# V2_0.net
KiCad netlist of a schematic drawn in EAGLE
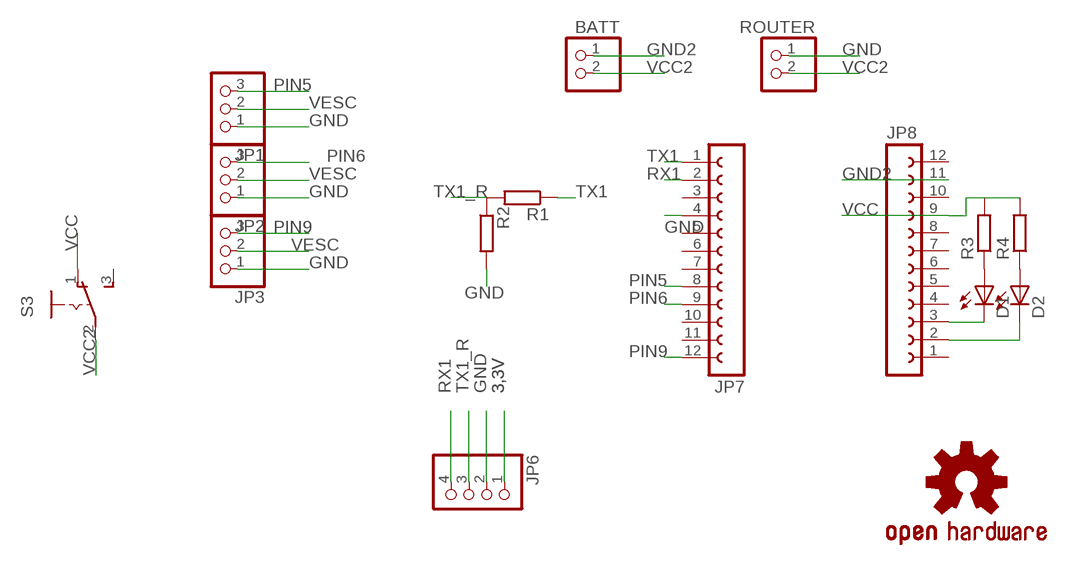
[diagram p0: schematic, sheet 1]

(export (version "E")
  (design (tool "Eeschema 10.0.6"))
  (components
    (comp (ref "BATT")
      (value "PINHD-1X2/90")
      (footprint "eagle-import:1X02_90")
      (libsource (lib "eagle-import") (part "PINHD-1X2/90"))
    )
    (comp (ref "D1")
      (value "LED3MM")
      (footprint "eagle-import:LED3MM")
      (libsource (lib "eagle-import") (part "LED3MM"))
    )
    (comp (ref "D2")
      (value "LED3MM")
      (footprint "eagle-import:LED3MM")
      (libsource (lib "eagle-import") (part "LED3MM"))
    )
    (comp (ref "JP1")
      (value "PINHD-1X3")
      (footprint "eagle-import:1X03")
      (libsource (lib "eagle-import") (part "PINHD-1X3"))
    )
    (comp (ref "JP2")
      (value "PINHD-1X3")
      (footprint "eagle-import:1X03")
      (libsource (lib "eagle-import") (part "PINHD-1X3"))
    )
    (comp (ref "JP3")
      (value "PINHD-1X3")
      (footprint "eagle-import:1X03")
      (libsource (lib "eagle-import") (part "PINHD-1X3"))
    )
    (comp (ref "JP6")
      (value "PINHD-1X4")
      (footprint "eagle-import:1X04")
      (libsource (lib "eagle-import") (part "PINHD-1X4"))
    )
    (comp (ref "JP7")
      (value "FE12-1")
      (footprint "eagle-import:FE12")
      (libsource (lib "eagle-import") (part "FE12-1"))
    )
    (comp (ref "JP8")
      (value "FE12-1")
      (footprint "eagle-import:FE12")
      (libsource (lib "eagle-import") (part "FE12-1"))
    )
    (comp (ref "R1")
      (value "R-EU_0204/7")
      (footprint "eagle-import:0204_7")
      (libsource (lib "eagle-import") (part "R-EU_0204/7"))
    )
    (comp (ref "R2")
      (value "R-EU_0204/7")
      (footprint "eagle-import:0204_7")
      (libsource (lib "eagle-import") (part "R-EU_0204/7"))
    )
    (comp (ref "R3")
      (value "R-EU_0204/7")
      (footprint "eagle-import:0204_7")
      (libsource (lib "eagle-import") (part "R-EU_0204/7"))
    )
    (comp (ref "R4")
      (value "R-EU_0204/7")
      (footprint "eagle-import:0204_7")
      (libsource (lib "eagle-import") (part "R-EU_0204/7"))
    )
    (comp (ref "ROUTER")
      (value "PINHD-1X2/90")
      (footprint "eagle-import:1X02_90")
      (libsource (lib "eagle-import") (part "PINHD-1X2/90"))
    )
    (comp (ref "S3")
      (value "M251")
      (footprint "eagle-import:M251")
      (libsource (lib "eagle-import") (part "M251"))
    )
    (comp (ref "U$2")
      (value "OSHW-LOGOS")
      (footprint "eagle-import:OSHW-LOGO-S")
      (libsource (lib "eagle-import") (part "OSHW-LOGOS"))
    )
  )
  (nets
    (net (code "1") (name "/3,3V") (class "Default")
      (node (ref "JP6") (pin "1") (pinfunction "1_1") (pintype "passive"))
    )
    (net (code "2") (name "/GND") (class "Default")
      (node (ref "JP1") (pin "1") (pinfunction "1_1") (pintype "passive"))
      (node (ref "JP2") (pin "1") (pinfunction "1_1") (pintype "passive"))
      (node (ref "JP3") (pin "1") (pinfunction "1_1") (pintype "passive"))
      (node (ref "JP6") (pin "2") (pinfunction "2_2") (pintype "passive"))
      (node (ref "JP7") (pin "4") (pinfunction "4_4") (pintype "passive"))
      (node (ref "R2") (pin "2") (pinfunction "2_2") (pintype "passive"))
      (node (ref "ROUTER") (pin "1") (pinfunction "1_1") (pintype "passive"))
    )
    (net (code "3") (name "/GND2") (class "Default")
      (node (ref "BATT") (pin "1") (pinfunction "1_1") (pintype "passive"))
      (node (ref "JP8") (pin "11") (pinfunction "11_11") (pintype "passive"))
    )
    (net (code "4") (name "/PIN5") (class "Default")
      (node (ref "JP1") (pin "3") (pinfunction "3_3") (pintype "passive"))
      (node (ref "JP7") (pin "8") (pinfunction "8_8") (pintype "passive"))
    )
    (net (code "5") (name "/PIN6") (class "Default")
      (node (ref "JP2") (pin "3") (pinfunction "3_3") (pintype "passive"))
      (node (ref "JP7") (pin "9") (pinfunction "9_9") (pintype "passive"))
    )
    (net (code "6") (name "/PIN9") (class "Default")
      (node (ref "JP3") (pin "3") (pinfunction "3_3") (pintype "passive"))
      (node (ref "JP7") (pin "12") (pinfunction "12_12") (pintype "passive"))
    )
    (net (code "7") (name "/RX1") (class "Default")
      (node (ref "JP6") (pin "4") (pinfunction "4_4") (pintype "passive"))
      (node (ref "JP7") (pin "2") (pinfunction "2_2") (pintype "passive"))
    )
    (net (code "8") (name "/TX1") (class "Default")
      (node (ref "JP7") (pin "1") (pinfunction "1_1") (pintype "passive"))
      (node (ref "R1") (pin "1") (pinfunction "1_1") (pintype "passive"))
    )
    (net (code "9") (name "/TX1_R") (class "Default")
      (node (ref "JP6") (pin "3") (pinfunction "3_3") (pintype "passive"))
      (node (ref "R1") (pin "2") (pinfunction "2_2") (pintype "passive"))
      (node (ref "R2") (pin "1") (pinfunction "1_1") (pintype "passive"))
    )
    (net (code "10") (name "/VCC") (class "Default")
      (node (ref "JP8") (pin "9") (pinfunction "9_9") (pintype "passive"))
      (node (ref "R3") (pin "2") (pinfunction "2_2") (pintype "passive"))
      (node (ref "R4") (pin "2") (pinfunction "2_2") (pintype "passive"))
      (node (ref "S3") (pin "1") (pinfunction "O_1") (pintype "passive"))
    )
    (net (code "11") (name "/VCC2") (class "Default")
      (node (ref "BATT") (pin "2") (pinfunction "2_2") (pintype "passive"))
      (node (ref "ROUTER") (pin "2") (pinfunction "2_2") (pintype "passive"))
      (node (ref "S3") (pin "2") (pinfunction "P_2") (pintype "passive"))
    )
    (net (code "12") (name "/VESC") (class "Default")
      (node (ref "JP1") (pin "2") (pinfunction "2_2") (pintype "passive"))
      (node (ref "JP2") (pin "2") (pinfunction "2_2") (pintype "passive"))
      (node (ref "JP3") (pin "2") (pinfunction "2_2") (pintype "passive"))
    )
    (net (code "13") (name "Net-(D1-C)") (class "Default")
      (node (ref "D1") (pin "K") (pinfunction "C_K") (pintype "passive"))
      (node (ref "JP8") (pin "3") (pinfunction "3_3") (pintype "passive"))
    )
    (net (code "14") (name "Net-(D1-PadA)") (class "Default")
      (node (ref "D1") (pin "A") (pinfunction "A_A") (pintype "passive"))
      (node (ref "R3") (pin "1") (pinfunction "1_1") (pintype "passive"))
    )
    (net (code "15") (name "Net-(D2-C)") (class "Default")
      (node (ref "D2") (pin "K") (pinfunction "C_K") (pintype "passive"))
      (node (ref "JP8") (pin "2") (pinfunction "2_2") (pintype "passive"))
    )
    (net (code "16") (name "Net-(D2-PadA)") (class "Default")
      (node (ref "D2") (pin "A") (pinfunction "A_A") (pintype "passive"))
      (node (ref "R4") (pin "1") (pinfunction "1_1") (pintype "passive"))
    )
    (net (code "17") (name "unconnected-(JP7-Pad3)") (class "Default")
      (node (ref "JP7") (pin "3") (pinfunction "3_3") (pintype "passive"))
    )
    (net (code "18") (name "unconnected-(JP7-Pad5)") (class "Default")
      (node (ref "JP7") (pin "5") (pinfunction "5_5") (pintype "passive"))
    )
    (net (code "19") (name "unconnected-(JP7-Pad6)") (class "Default")
      (node (ref "JP7") (pin "6") (pinfunction "6_6") (pintype "passive"))
    )
    (net (code "20") (name "unconnected-(JP7-Pad7)") (class "Default")
      (node (ref "JP7") (pin "7") (pinfunction "7_7") (pintype "passive"))
    )
    (net (code "21") (name "unconnected-(JP7-Pad10)") (class "Default")
      (node (ref "JP7") (pin "10") (pinfunction "10_10") (pintype "passive"))
    )
    (net (code "22") (name "unconnected-(JP7-Pad11)") (class "Default")
      (node (ref "JP7") (pin "11") (pinfunction "11_11") (pintype "passive"))
    )
    (net (code "23") (name "unconnected-(JP8-Pad1)") (class "Default")
      (node (ref "JP8") (pin "1") (pinfunction "1_1") (pintype "passive"))
    )
    (net (code "24") (name "unconnected-(JP8-Pad4)") (class "Default")
      (node (ref "JP8") (pin "4") (pinfunction "4_4") (pintype "passive"))
    )
    (net (code "25") (name "unconnected-(JP8-Pad5)") (class "Default")
      (node (ref "JP8") (pin "5") (pinfunction "5_5") (pintype "passive"))
    )
    (net (code "26") (name "unconnected-(JP8-Pad6)") (class "Default")
      (node (ref "JP8") (pin "6") (pinfunction "6_6") (pintype "passive"))
    )
    (net (code "27") (name "unconnected-(JP8-Pad7)") (class "Default")
      (node (ref "JP8") (pin "7") (pinfunction "7_7") (pintype "passive"))
    )
    (net (code "28") (name "unconnected-(JP8-Pad8)") (class "Default")
      (node (ref "JP8") (pin "8") (pinfunction "8_8") (pintype "passive"))
    )
    (net (code "29") (name "unconnected-(JP8-Pad10)") (class "Default")
      (node (ref "JP8") (pin "10") (pinfunction "10_10") (pintype "passive"))
    )
    (net (code "30") (name "unconnected-(JP8-Pad12)") (class "Default")
      (node (ref "JP8") (pin "12") (pinfunction "12_12") (pintype "passive"))
    )
    (net (code "31") (name "unconnected-(S3-S-Pad3)") (class "Default")
      (node (ref "S3") (pin "3") (pinfunction "S_3") (pintype "passive"))
    )
  )
)
